# cb_v2.net
KiCad netlist of a schematic drawn in Altium Designer
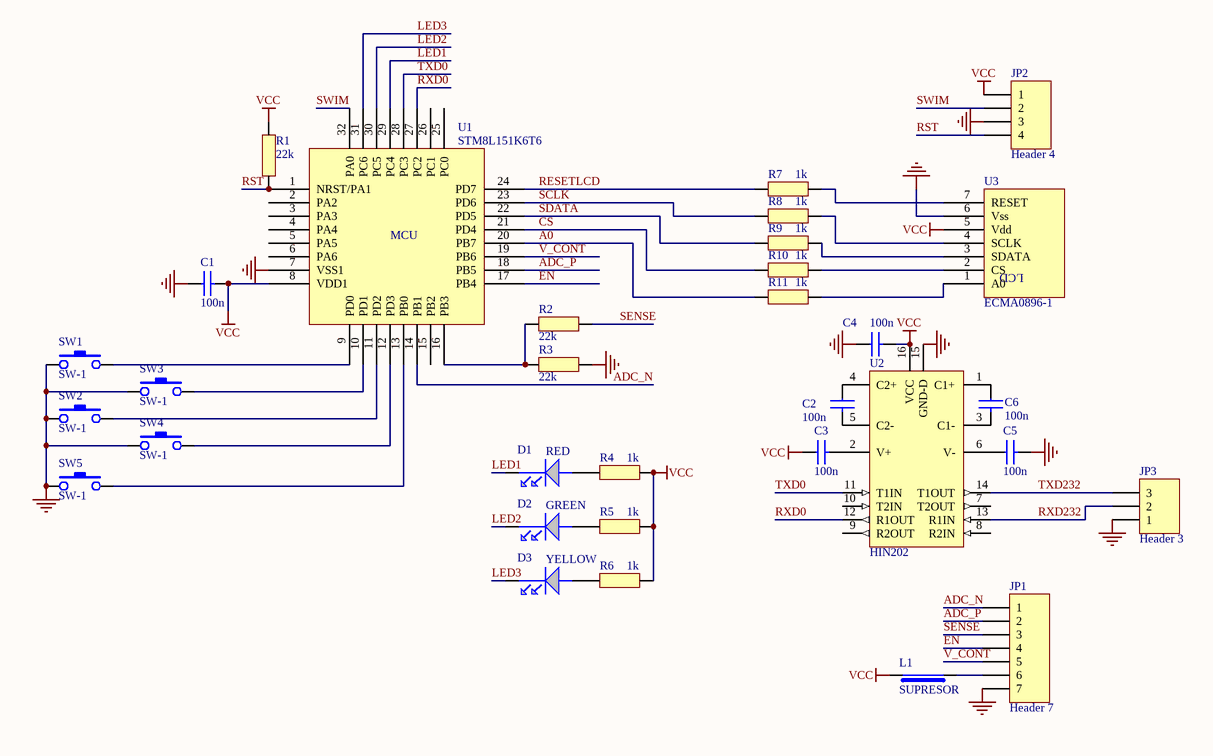
[diagram p0: cb_v2.SchDoc]

(export (version "E")
  (design (tool "Eeschema 10.0.6"))
  (components
    (comp (ref "C1") (value "100n") (footprint "C-0805") (libsource (lib "RCS-Discret") (part "C")))
    (comp (ref "C2") (value "100n") (footprint "C-0805") (libsource (lib "RCS-Discret") (part "C")))
    (comp (ref "C3") (value "100n") (footprint "C-0805") (libsource (lib "RCS-Discret") (part "C")))
    (comp (ref "C4") (value "100n") (footprint "C-0805") (libsource (lib "RCS-Discret") (part "C")))
    (comp (ref "C5") (value "100n") (footprint "C-0805") (libsource (lib "RCS-Discret") (part "C")))
    (comp (ref "C6") (value "100n") (footprint "C-0805") (libsource (lib "RCS-Discret") (part "C")))
    (comp (ref "D1") (value "RED") (footprint "LED-DIP-1") (libsource (lib "RCS-Discret") (part "LED")))
    (comp (ref "D2") (value "GREEN") (footprint "LED-DIP-1") (libsource (lib "RCS-Discret") (part "LED")))
    (comp (ref "D3") (value "YELLOW") (footprint "LED-DIP-1") (libsource (lib "RCS-Discret") (part "LED")))
    (comp (ref "JP1")
      (value "Header 7")
      (footprint "HDR1X7")
      (description "Header, 7-Pin")
      (fields (field (name "PUBLISHER") "Altium Limited"))
      (libsource (lib "Miscellaneous Connectors") (part "Header 7"))
    )
    (comp (ref "JP2")
      (value "Header 4")
      (footprint "HDR1X4")
      (description "Header, 4-Pin")
      (fields (field (name "PUBLISHER") "Altium Limited"))
      (libsource (lib "Miscellaneous Connectors") (part "Header 4"))
    )
    (comp (ref "JP3")
      (value "Header 3")
      (footprint "HDR1X3")
      (description "Header, 3-Pin")
      (fields (field (name "PUBLISHER") "Altium Limited"))
      (libsource (lib "Miscellaneous Connectors") (part "Header 3"))
    )
    (comp (ref "L1")
      (value "SUPRESOR")
      (footprint "R-1206")
      (libsource (lib "RCS-Discret") (part "SUPRESOR"))
    )
    (comp (ref "R1") (value "22k") (footprint "R-0805") (libsource (lib "") (part "R_2")))
    (comp (ref "R2") (value "22k") (footprint "R-0805") (libsource (lib "") (part "R_3")))
    (comp (ref "R3") (value "22k") (footprint "R-0805") (libsource (lib "RCS-Discret") (part "R")))
    (comp (ref "R4") (value "1k") (footprint "R-0805") (libsource (lib "RCS-Discret") (part "R")))
    (comp (ref "R5") (value "1k") (footprint "R-0805") (libsource (lib "RCS-Discret") (part "R")))
    (comp (ref "R6") (value "1k") (footprint "R-0805") (libsource (lib "RCS-Discret") (part "R")))
    (comp (ref "R7") (value "1k") (footprint "R-0805") (libsource (lib "") (part "R_1")))
    (comp (ref "R8") (value "1k") (footprint "R-0805") (libsource (lib "") (part "R_1")))
    (comp (ref "R9") (value "1k") (footprint "R-0805") (libsource (lib "") (part "R_1")))
    (comp (ref "R10") (value "1k") (footprint "R-0805") (libsource (lib "") (part "R_1")))
    (comp (ref "R11") (value "1k") (footprint "R-0805") (libsource (lib "") (part "R_1")))
    (comp (ref "SW1") (value "SW-1") (footprint "SW4-2") (libsource (lib "RCS-Connect&pushe") (part "SW-1")))
    (comp (ref "SW2") (value "SW-1") (footprint "SW4-2") (libsource (lib "RCS-Connect&pushe") (part "SW-1")))
    (comp (ref "SW3") (value "SW-1") (footprint "SW4-2") (libsource (lib "RCS-Connect&pushe") (part "SW-1")))
    (comp (ref "SW4") (value "SW-1") (footprint "SW4-2") (libsource (lib "RCS-Connect&pushe") (part "SW-1")))
    (comp (ref "SW5") (value "SW-1") (footprint "SW4-2") (libsource (lib "RCS-Connect&pushe") (part "SW-1")))
    (comp (ref "U1")
      (value "STM8L151K6T6")
      (footprint "QFP32")
      (libsource (lib "RCS-IMS") (part "STM32L151"))
    )
    (comp (ref "U2")
      (value "HIN202")
      (footprint "SO16-(SOT-109-1)")
      (description "RS232 driver")
      (libsource (lib "RCS-IMS") (part "HIN202"))
    )
    (comp (ref "U3")
      (value "ECMA0896-1")
      (footprint "ECMA0896")
      (libsource (lib "RCS-IMS") (part "ECMA0896"))
    )
  )
  (nets
    (net (code "1") (name "/A0") (class "Default")
      (node (ref "R11") (pin "1") (pinfunction "1_1") (pintype "passive"))
      (node (ref "U1") (pin "20") (pinfunction "PB7_20") (pintype "passive"))
    )
    (net (code "2") (name "/ADC_N") (class "Default")
      (node (ref "JP1") (pin "1") (pinfunction "1_1") (pintype "passive"))
      (node (ref "U1") (pin "14") (pinfunction "PB1_14") (pintype "passive"))
    )
    (net (code "3") (name "/ADC_P") (class "Default")
      (node (ref "JP1") (pin "2") (pinfunction "2_2") (pintype "passive"))
      (node (ref "U1") (pin "18") (pinfunction "PB5_18") (pintype "passive"))
    )
    (net (code "4") (name "/CS") (class "Default")
      (node (ref "R10") (pin "1") (pinfunction "1_1") (pintype "passive"))
      (node (ref "U1") (pin "21") (pinfunction "PD4_21") (pintype "passive"))
    )
    (net (code "5") (name "/EN") (class "Default")
      (node (ref "JP1") (pin "4") (pinfunction "4_4") (pintype "passive"))
      (node (ref "U1") (pin "17") (pinfunction "PB4_17") (pintype "passive"))
    )
    (net (code "6") (name "/LED1") (class "Default")
      (node (ref "D1") (pin "K") (pinfunction "CATHODE_K") (pintype "passive"))
      (node (ref "U1") (pin "29") (pinfunction "PC4_29") (pintype "passive"))
    )
    (net (code "7") (name "/LED2") (class "Default")
      (node (ref "D2") (pin "K") (pinfunction "CATHODE_K") (pintype "passive"))
      (node (ref "U1") (pin "30") (pinfunction "PC5_30") (pintype "passive"))
    )
    (net (code "8") (name "/LED3") (class "Default")
      (node (ref "D3") (pin "K") (pinfunction "CATHODE_K") (pintype "passive"))
      (node (ref "U1") (pin "31") (pinfunction "PC6_31") (pintype "passive"))
    )
    (net (code "9") (name "/RESETLCD") (class "Default")
      (node (ref "R7") (pin "1") (pinfunction "1_1") (pintype "passive"))
      (node (ref "U1") (pin "24") (pinfunction "PD7_24") (pintype "passive"))
    )
    (net (code "10") (name "/RST") (class "Default")
      (node (ref "JP2") (pin "4") (pinfunction "4_4") (pintype "passive"))
      (node (ref "R1") (pin "2") (pinfunction "2_2") (pintype "passive"))
      (node (ref "U1") (pin "1") (pinfunction "NRST/PA1_1") (pintype "passive"))
    )
    (net (code "11") (name "/RXD0") (class "Default")
      (node (ref "U1") (pin "27") (pinfunction "PC2_27") (pintype "passive"))
      (node (ref "U2") (pin "12") (pinfunction "R1OUT_12") (pintype "output"))
    )
    (net (code "12") (name "/RXD232") (class "Default")
      (node (ref "JP3") (pin "2") (pinfunction "2_2") (pintype "passive"))
      (node (ref "U2") (pin "13") (pinfunction "R1IN_13") (pintype "input"))
    )
    (net (code "13") (name "/SCLK") (class "Default")
      (node (ref "R8") (pin "1") (pinfunction "1_1") (pintype "passive"))
      (node (ref "U1") (pin "23") (pinfunction "PD6_23") (pintype "passive"))
    )
    (net (code "14") (name "/SDATA") (class "Default")
      (node (ref "R9") (pin "1") (pinfunction "1_1") (pintype "passive"))
      (node (ref "U1") (pin "22") (pinfunction "PD5_22") (pintype "passive"))
    )
    (net (code "15") (name "/SENSE") (class "Default")
      (node (ref "JP1") (pin "3") (pinfunction "3_3") (pintype "passive"))
      (node (ref "R2") (pin "1") (pinfunction "1_1") (pintype "passive"))
    )
    (net (code "16") (name "/SWIM") (class "Default")
      (node (ref "JP2") (pin "2") (pinfunction "2_2") (pintype "passive"))
      (node (ref "U1") (pin "32") (pinfunction "PA0_32") (pintype "passive"))
    )
    (net (code "17") (name "/TXD0") (class "Default")
      (node (ref "U1") (pin "28") (pinfunction "PC3_28") (pintype "passive"))
      (node (ref "U2") (pin "11") (pinfunction "T1IN_11") (pintype "input"))
    )
    (net (code "18") (name "/TXD232") (class "Default")
      (node (ref "JP3") (pin "3") (pinfunction "3_3") (pintype "passive"))
      (node (ref "U2") (pin "14") (pinfunction "T1OUT_14") (pintype "output"))
    )
    (net (code "19") (name "/V_CONT") (class "Default")
      (node (ref "JP1") (pin "5") (pinfunction "5_5") (pintype "passive"))
      (node (ref "U1") (pin "19") (pinfunction "PB6_19") (pintype "passive"))
    )
    (net (code "20") (name "GND") (class "Default")
      (node (ref "C1") (pin "1") (pinfunction "1_1") (pintype "passive"))
      (node (ref "C4") (pin "1") (pinfunction "1_1") (pintype "passive"))
      (node (ref "C5") (pin "2") (pinfunction "2_2") (pintype "passive"))
      (node (ref "JP1") (pin "7") (pinfunction "7_7") (pintype "passive"))
      (node (ref "JP2") (pin "3") (pinfunction "3_3") (pintype "passive"))
      (node (ref "JP3") (pin "1") (pinfunction "1_1") (pintype "passive"))
      (node (ref "R3") (pin "2") (pinfunction "2_2") (pintype "passive"))
      (node (ref "SW1") (pin "2") (pinfunction "2_2") (pintype "passive"))
      (node (ref "SW2") (pin "2") (pinfunction "2_2") (pintype "passive"))
      (node (ref "SW3") (pin "2") (pinfunction "2_2") (pintype "passive"))
      (node (ref "SW4") (pin "2") (pinfunction "2_2") (pintype "passive"))
      (node (ref "SW5") (pin "2") (pinfunction "2_2") (pintype "passive"))
      (node (ref "U1") (pin "7") (pinfunction "VSS1_7") (pintype "passive"))
      (node (ref "U2") (pin "15") (pinfunction "GND-D_15") (pintype "power_in"))
      (node (ref "U3") (pin "6") (pinfunction "Vss_6") (pintype "passive"))
    )
    (net (code "21") (name "Net-(D1-ANODE)") (class "Default")
      (node (ref "D1") (pin "A") (pinfunction "ANODE_A") (pintype "passive"))
      (node (ref "R4") (pin "1") (pinfunction "1_1") (pintype "passive"))
    )
    (net (code "22") (name "Net-(D2-ANODE)") (class "Default")
      (node (ref "D2") (pin "A") (pinfunction "ANODE_A") (pintype "passive"))
      (node (ref "R5") (pin "1") (pinfunction "1_1") (pintype "passive"))
    )
    (net (code "23") (name "Net-(D3-ANODE)") (class "Default")
      (node (ref "D3") (pin "A") (pinfunction "ANODE_A") (pintype "passive"))
      (node (ref "R6") (pin "1") (pinfunction "1_1") (pintype "passive"))
    )
    (net (code "24") (name "Net-(JP1-Pad6)") (class "Default")
      (node (ref "JP1") (pin "6") (pinfunction "6_6") (pintype "passive"))
      (node (ref "L1") (pin "1") (pinfunction "1_1") (pintype "passive"))
    )
    (net (code "25") (name "Net-(U1-PB0)") (class "Default")
      (node (ref "SW5") (pin "1") (pinfunction "1_1") (pintype "passive"))
      (node (ref "U1") (pin "13") (pinfunction "PB0_13") (pintype "passive"))
    )
    (net (code "26") (name "Net-(U1-PB3)") (class "Default")
      (node (ref "R2") (pin "2") (pinfunction "2_2") (pintype "passive"))
      (node (ref "R3") (pin "1") (pinfunction "1_1") (pintype "passive"))
      (node (ref "U1") (pin "16") (pinfunction "PB3_16") (pintype "passive"))
    )
    (net (code "27") (name "Net-(U1-PD0)") (class "Default")
      (node (ref "SW1") (pin "1") (pinfunction "1_1") (pintype "passive"))
      (node (ref "U1") (pin "9") (pinfunction "PD0_9") (pintype "passive"))
    )
    (net (code "28") (name "Net-(U1-PD1)") (class "Default")
      (node (ref "SW3") (pin "1") (pinfunction "1_1") (pintype "passive"))
      (node (ref "U1") (pin "10") (pinfunction "PD1_10") (pintype "passive"))
    )
    (net (code "29") (name "Net-(U1-PD2)") (class "Default")
      (node (ref "SW2") (pin "1") (pinfunction "1_1") (pintype "passive"))
      (node (ref "U1") (pin "11") (pinfunction "PD2_11") (pintype "passive"))
    )
    (net (code "30") (name "Net-(U1-PD3)") (class "Default")
      (node (ref "SW4") (pin "1") (pinfunction "1_1") (pintype "passive"))
      (node (ref "U1") (pin "12") (pinfunction "PD3_12") (pintype "passive"))
    )
    (net (code "31") (name "Net-(U2-C1+)") (class "Default")
      (node (ref "C6") (pin "1") (pinfunction "1_1") (pintype "passive"))
      (node (ref "U2") (pin "1") (pinfunction "C1+_1") (pintype "passive"))
    )
    (net (code "32") (name "Net-(U2-C1-)") (class "Default")
      (node (ref "C6") (pin "2") (pinfunction "2_2") (pintype "passive"))
      (node (ref "U2") (pin "3") (pinfunction "C1-_3") (pintype "passive"))
    )
    (net (code "33") (name "Net-(U2-C2+)") (class "Default")
      (node (ref "C2") (pin "1") (pinfunction "1_1") (pintype "passive"))
      (node (ref "U2") (pin "4") (pinfunction "C2+_4") (pintype "passive"))
    )
    (net (code "34") (name "Net-(U2-C2-)") (class "Default")
      (node (ref "C2") (pin "2") (pinfunction "2_2") (pintype "passive"))
      (node (ref "U2") (pin "5") (pinfunction "C2-_5") (pintype "passive"))
    )
    (net (code "35") (name "Net-(U2-V+)") (class "Default")
      (node (ref "C3") (pin "2") (pinfunction "2_2") (pintype "passive"))
      (node (ref "U2") (pin "2") (pinfunction "V+_2") (pintype "passive"))
    )
    (net (code "36") (name "Net-(U2-V-)") (class "Default")
      (node (ref "C5") (pin "1") (pinfunction "1_1") (pintype "passive"))
      (node (ref "U2") (pin "6") (pinfunction "V-_6") (pintype "passive"))
    )
    (net (code "37") (name "Net-(U3-A0)") (class "Default")
      (node (ref "R11") (pin "2") (pinfunction "2_2") (pintype "passive"))
      (node (ref "U3") (pin "1") (pinfunction "A0_1") (pintype "passive"))
    )
    (net (code "38") (name "Net-(U3-CS)") (class "Default")
      (node (ref "R10") (pin "2") (pinfunction "2_2") (pintype "passive"))
      (node (ref "U3") (pin "2") (pinfunction "CS_2") (pintype "passive"))
    )
    (net (code "39") (name "Net-(U3-RESET)") (class "Default")
      (node (ref "R7") (pin "2") (pinfunction "2_2") (pintype "passive"))
      (node (ref "U3") (pin "7") (pinfunction "RESET_7") (pintype "passive"))
    )
    (net (code "40") (name "Net-(U3-SCLK)") (class "Default")
      (node (ref "R8") (pin "2") (pinfunction "2_2") (pintype "passive"))
      (node (ref "U3") (pin "4") (pinfunction "SCLK_4") (pintype "passive"))
    )
    (net (code "41") (name "Net-(U3-SDATA)") (class "Default")
      (node (ref "R9") (pin "2") (pinfunction "2_2") (pintype "passive"))
      (node (ref "U3") (pin "3") (pinfunction "SDATA_3") (pintype "passive"))
    )
    (net (code "42") (name "VCC") (class "Default")
      (node (ref "C1") (pin "2") (pinfunction "2_2") (pintype "passive"))
      (node (ref "C3") (pin "1") (pinfunction "1_1") (pintype "passive"))
      (node (ref "C4") (pin "2") (pinfunction "2_2") (pintype "passive"))
      (node (ref "JP2") (pin "1") (pinfunction "1_1") (pintype "passive"))
      (node (ref "L1") (pin "2") (pinfunction "2_2") (pintype "passive"))
      (node (ref "R1") (pin "1") (pinfunction "1_1") (pintype "passive"))
      (node (ref "R4") (pin "2") (pinfunction "2_2") (pintype "passive"))
      (node (ref "R5") (pin "2") (pinfunction "2_2") (pintype "passive"))
      (node (ref "R6") (pin "2") (pinfunction "2_2") (pintype "passive"))
      (node (ref "U1") (pin "8") (pinfunction "VDD1_8") (pintype "passive"))
      (node (ref "U2") (pin "16") (pinfunction "VCC_16") (pintype "power_in"))
      (node (ref "U3") (pin "5") (pinfunction "Vdd_5") (pintype "passive"))
    )
    (net (code "43") (name "unconnected-(U1-PA2-Pad2)") (class "Default")
      (node (ref "U1") (pin "2") (pinfunction "PA2_2") (pintype "passive"))
    )
    (net (code "44") (name "unconnected-(U1-PA3-Pad3)") (class "Default")
      (node (ref "U1") (pin "3") (pinfunction "PA3_3") (pintype "passive"))
    )
    (net (code "45") (name "unconnected-(U1-PA4-Pad4)") (class "Default")
      (node (ref "U1") (pin "4") (pinfunction "PA4_4") (pintype "passive"))
    )
    (net (code "46") (name "unconnected-(U1-PA5-Pad5)") (class "Default")
      (node (ref "U1") (pin "5") (pinfunction "PA5_5") (pintype "passive"))
    )
    (net (code "47") (name "unconnected-(U1-PA6-Pad6)") (class "Default")
      (node (ref "U1") (pin "6") (pinfunction "PA6_6") (pintype "passive"))
    )
    (net (code "48") (name "unconnected-(U1-PB2-Pad15)") (class "Default")
      (node (ref "U1") (pin "15") (pinfunction "PB2_15") (pintype "passive"))
    )
    (net (code "49") (name "unconnected-(U1-PC0-Pad25)") (class "Default")
      (node (ref "U1") (pin "25") (pinfunction "PC0_25") (pintype "passive"))
    )
    (net (code "50") (name "unconnected-(U1-PC1-Pad26)") (class "Default")
      (node (ref "U1") (pin "26") (pinfunction "PC1_26") (pintype "passive"))
    )
    (net (code "51") (name "unconnected-(U2-R2IN-Pad8)") (class "Default")
      (node (ref "U2") (pin "8") (pinfunction "R2IN_8") (pintype "input"))
    )
    (net (code "52") (name "unconnected-(U2-R2OUT-Pad9)") (class "Default")
      (node (ref "U2") (pin "9") (pinfunction "R2OUT_9") (pintype "output"))
    )
    (net (code "53") (name "unconnected-(U2-T2IN-Pad10)") (class "Default")
      (node (ref "U2") (pin "10") (pinfunction "T2IN_10") (pintype "input"))
    )
    (net (code "54") (name "unconnected-(U2-T2OUT-Pad7)") (class "Default")
      (node (ref "U2") (pin "7") (pinfunction "T2OUT_7") (pintype "output"))
    )
  )
)
